# CV_Power-Pause_LED_Mod_PCB_v1_2.net
KiCad netlist of a schematic drawn in EAGLE
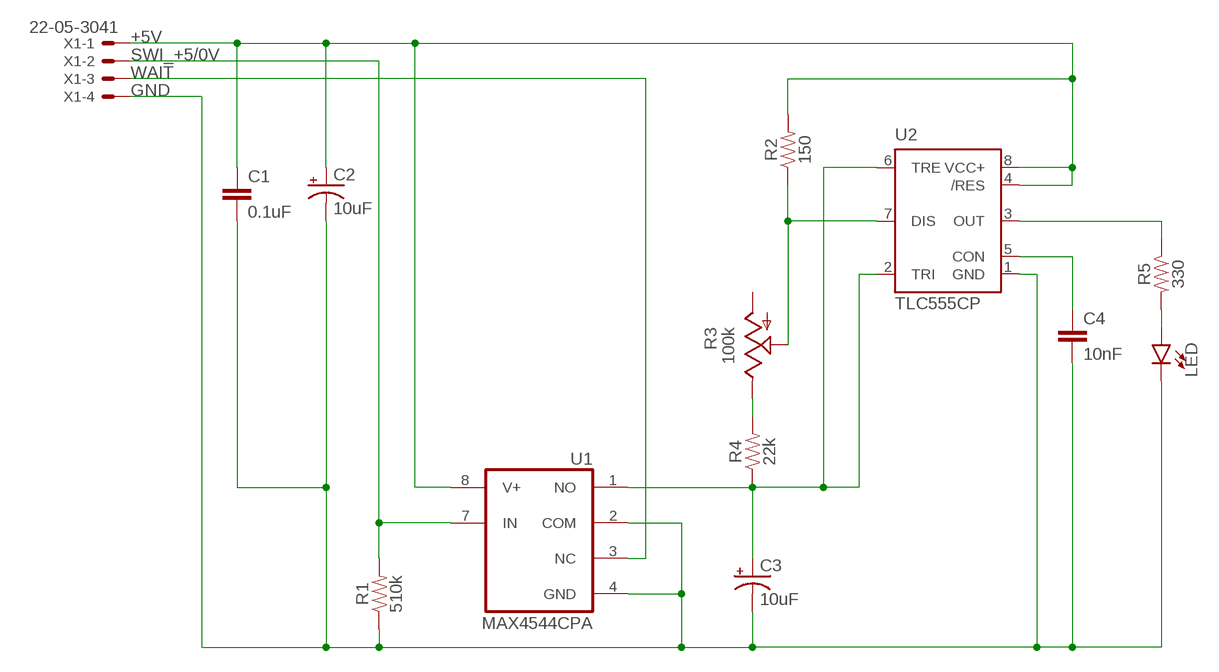
[diagram p0: schematic, sheet 1]

(export (version "E")
  (design (tool "Eeschema 10.0.6"))
  (components
    (comp (ref "C1")
      (value "0.1uF")
      (footprint "eagle-import:CAP-PTH-SMALL2")
      (libsource (lib "eagle-import") (part "CAPPTH2"))
    )
    (comp (ref "C2")
      (value "10uF")
      (footprint "eagle-import:E2,5-6")
      (libsource (lib "eagle-import") (part "CPOL-USE2.5-6"))
    )
    (comp (ref "C3")
      (value "10uF")
      (footprint "eagle-import:E2,5-6")
      (libsource (lib "eagle-import") (part "CPOL-USE2.5-6"))
    )
    (comp (ref "C4")
      (value "10nF")
      (footprint "eagle-import:CAP-PTH-SMALL2")
      (libsource (lib "eagle-import") (part "CAPPTH2"))
    )
    (comp (ref "LED")
      (value "LED5MM")
      (footprint "eagle-import:LED_5MM")
      (libsource (lib "eagle-import") (part "LED5MM"))
    )
    (comp (ref "R1")
      (value "510k")
      (footprint "eagle-import:AXIAL-0.3")
      (libsource (lib "eagle-import") (part "RESISTORAXIAL-0.3"))
    )
    (comp (ref "R2")
      (value "150")
      (footprint "eagle-import:AXIAL-0.3")
      (libsource (lib "eagle-import") (part "RESISTORAXIAL-0.3"))
    )
    (comp (ref "R3")
      (value "100k")
      (footprint "eagle-import:CT6")
      (libsource (lib "eagle-import") (part "TRIM_US-CT6"))
    )
    (comp (ref "R4")
      (value "22k")
      (footprint "eagle-import:AXIAL-0.3")
      (libsource (lib "eagle-import") (part "RESISTORAXIAL-0.3"))
    )
    (comp (ref "R5")
      (value "330")
      (footprint "eagle-import:AXIAL-0.3")
      (libsource (lib "eagle-import") (part "RESISTORAXIAL-0.3"))
    )
    (comp (ref "U1")
      (value "MAX4544CPA")
      (footprint "eagle-import:DIP08")
      (libsource (lib "eagle-import") (part "MAX4544CPA"))
    )
    (comp (ref "U2")
      (value "TLC555CP")
      (footprint "eagle-import:DIP08")
      (libsource (lib "eagle-import") (part "555P"))
    )
    (comp (ref "X1")
      (value "22-05-3041")
      (footprint "eagle-import:22-05-3041")
      (fields (field (name "MF") "MOLEX"))
      (libsource (lib "eagle-import") (part "22-05-3041"))
    )
  )
  (nets
    (net (code "1") (name "/+5V") (class "Default")
      (node (ref "C1") (pin "1") (pinfunction "1_1") (pintype "passive"))
      (node (ref "C2") (pin "+") (pinfunction "+_+") (pintype "passive"))
      (node (ref "R2") (pin "P$2") (pinfunction "2_P$2") (pintype "passive"))
      (node (ref "U1") (pin "8") (pinfunction "V+_8") (pintype "power_in"))
      (node (ref "U2") (pin "4") (pinfunction "/RES_4") (pintype "input"))
      (node (ref "U2") (pin "8") (pinfunction "VCC+_8") (pintype "power_in"))
      (node (ref "X1") (pin "1") (pinfunction "S_1") (pintype "passive"))
    )
    (net (code "2") (name "/GND") (class "Default")
      (node (ref "C1") (pin "2") (pinfunction "2_2") (pintype "passive"))
      (node (ref "C2") (pin "-") (pinfunction "-_-") (pintype "passive"))
      (node (ref "C3") (pin "-") (pinfunction "-_-") (pintype "passive"))
      (node (ref "C4") (pin "2") (pinfunction "2_2") (pintype "passive"))
      (node (ref "LED") (pin "K") (pinfunction "C_K") (pintype "passive"))
      (node (ref "R1") (pin "P$1") (pinfunction "1_P$1") (pintype "passive"))
      (node (ref "U1") (pin "2") (pinfunction "COM_2") (pintype "passive"))
      (node (ref "U1") (pin "4") (pinfunction "GND_4") (pintype "power_in"))
      (node (ref "U2") (pin "1") (pinfunction "GND_1") (pintype "power_in"))
      (node (ref "X1") (pin "4") (pinfunction "S_4") (pintype "passive"))
    )
    (net (code "3") (name "/SWI_+5{slash}0V") (class "Default")
      (node (ref "R1") (pin "P$2") (pinfunction "2_P$2") (pintype "passive"))
      (node (ref "U1") (pin "7") (pinfunction "IN_7") (pintype "input"))
      (node (ref "X1") (pin "2") (pinfunction "S_2") (pintype "passive"))
    )
    (net (code "4") (name "/WAIT") (class "Default")
      (node (ref "U1") (pin "3") (pinfunction "NC_3") (pintype "passive"))
      (node (ref "X1") (pin "3") (pinfunction "S_3") (pintype "passive"))
    )
    (net (code "5") (name "Net-(R2-1)") (class "Default")
      (node (ref "R2") (pin "P$1") (pinfunction "1_P$1") (pintype "passive"))
      (node (ref "R3") (pin "S") (pinfunction "S_S") (pintype "passive"))
      (node (ref "U2") (pin "7") (pinfunction "DIS_7") (pintype "input"))
    )
    (net (code "6") (name "Net-(R4-1)") (class "Default")
      (node (ref "C3") (pin "+") (pinfunction "+_+") (pintype "passive"))
      (node (ref "R4") (pin "P$1") (pinfunction "1_P$1") (pintype "passive"))
      (node (ref "U1") (pin "1") (pinfunction "NO_1") (pintype "passive"))
      (node (ref "U2") (pin "2") (pinfunction "TRI_2") (pintype "input"))
      (node (ref "U2") (pin "6") (pinfunction "TRE_6") (pintype "input"))
    )
    (net (code "7") (name "Net-(R4-2)") (class "Default")
      (node (ref "R3") (pin "E") (pinfunction "E_E") (pintype "passive"))
      (node (ref "R4") (pin "P$2") (pinfunction "2_P$2") (pintype "passive"))
    )
    (net (code "8") (name "Net-(R5-1)") (class "Default")
      (node (ref "R5") (pin "P$1") (pinfunction "1_P$1") (pintype "passive"))
      (node (ref "U2") (pin "3") (pinfunction "OUT_3") (pintype "output"))
    )
    (net (code "9") (name "Net-(R5-2)") (class "Default")
      (node (ref "LED") (pin "A") (pinfunction "A_A") (pintype "passive"))
      (node (ref "R5") (pin "P$2") (pinfunction "2_P$2") (pintype "passive"))
    )
    (net (code "10") (name "Net-(U2-CON)") (class "Default")
      (node (ref "C4") (pin "1") (pinfunction "1_1") (pintype "passive"))
      (node (ref "U2") (pin "5") (pinfunction "CON_5") (pintype "input"))
    )
    (net (code "11") (name "unconnected-(R3-PadA)") (class "Default")
      (node (ref "R3") (pin "A") (pinfunction "A_A") (pintype "passive"))
    )
  )
)
